# HS-IO_ESP32.net
KiCad netlist of a schematic drawn in Altium Designer
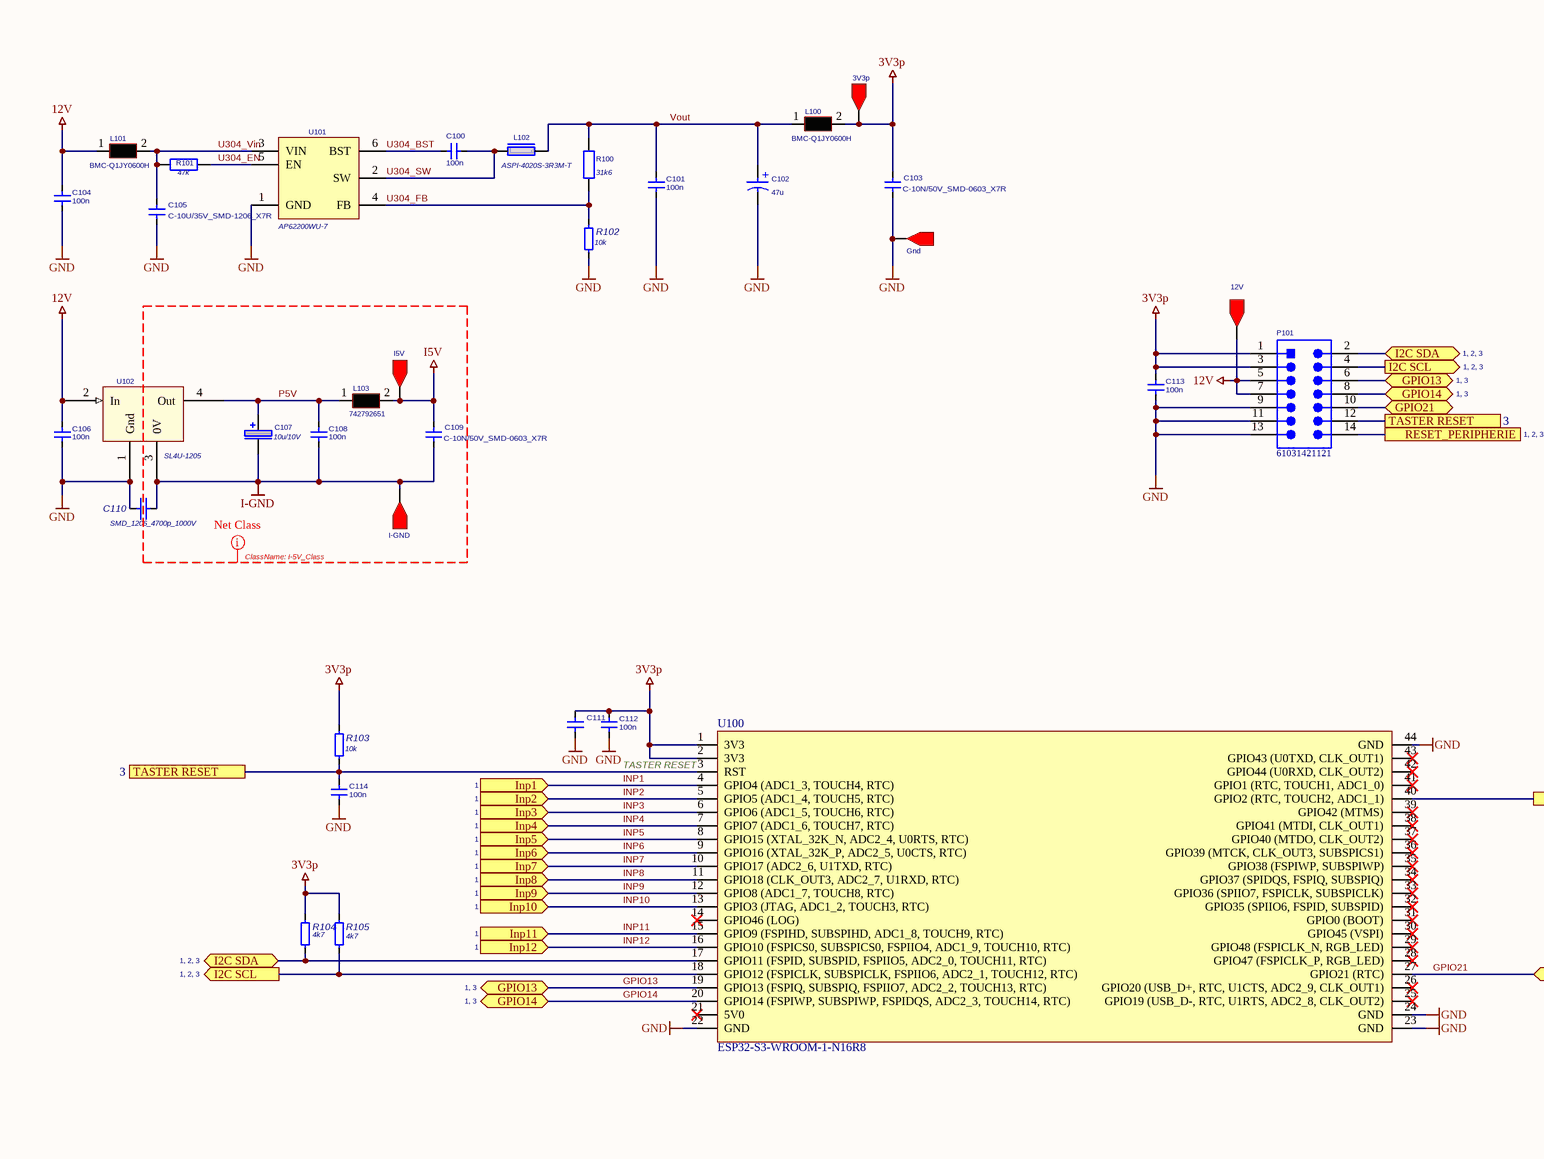
[diagram p0: HS-IO ESP32.SchDoc, left]
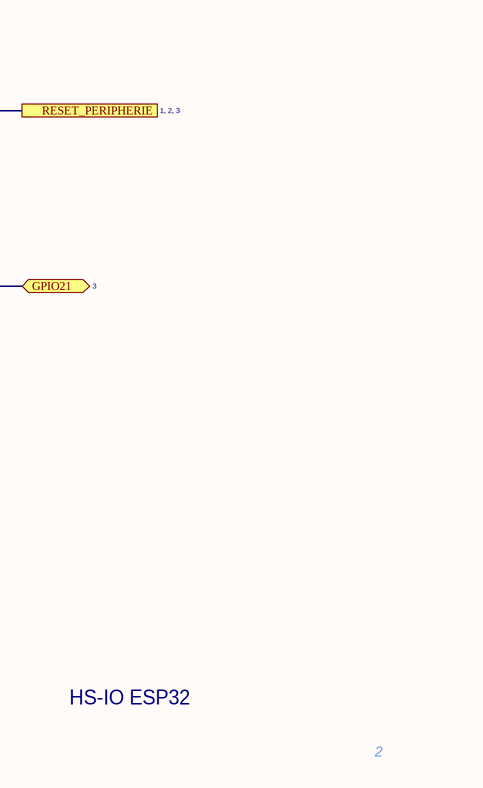
[diagram p1: HS-IO ESP32.SchDoc, right]

(export (version "E")
  (design (tool "Eeschema 10.0.6"))
  (components
    (comp (ref "3V3p")
      (value "(no part)")
      (footprint "TESTPOINT")
      (description "Test Point")
      (libsource (lib "FRAKO Kondensatoren- und Anlagenbau GmbH") (part "TESTPUNKT_1"))
    )
    (comp (ref "12V")
      (value "(no part)")
      (footprint "TESTPOINT")
      (description "Test Point")
      (libsource (lib "FRAKO Kondensatoren- und Anlagenbau GmbH") (part "TESTPUNKT_1"))
    )
    (comp (ref "C100")
      (value "100n")
      (footprint "CC1608-0603")
      (description "SMD0603, X7R, 15%, 50V, 100nF")
      (fields
        (field (name "MANUFACTURER") "KEMET")
        (field (name "MANUFACTURER PART NUMBER") "C0603C104K5RAC7867")
      )
      (libsource (lib "FRAKO Kondensatoren- und Anlagenbau GmbH") (part "C_SMD-0603"))
    )
    (comp (ref "C101")
      (value "100n")
      (footprint "CC1608-0603")
      (description "SMD0603, X7R, 15%, 50V, 100nF")
      (fields
        (field (name "MANUFACTURER") "KEMET")
        (field (name "MANUFACTURER PART NUMBER") "C0603C104K5RAC7867")
      )
      (libsource (lib "FRAKO Kondensatoren- und Anlagenbau GmbH") (part "C_SMD-0603"))
    )
    (comp (ref "C102")
      (value "47u")
      (footprint "WCAP-PSLP_D5H5.5")
      (description "WCAP-PSLP Aluminum Polymer Capacitor, V-Chip SMT, D5 x H5.5mm, 47µF, 6.3V")
      (fields
        (field (name "MANUFACTURER PART NUMBER") "875105142001")
        (field (name "MANUFACTURER") "Wurth Elektronik")
      )
      (libsource (lib "FRAKO Kondensatoren- und Anlagenbau GmbH") (part "875105945001"))
    )
    (comp (ref "C103")
      (value "C-10N/50V_SMD-0603_X7R")
      (footprint "0603_SMD_T")
      (description "C 10N/50V, SMD-0603, X7R")
      (fields
        (field (name "MANUFACTURER") "AVX GMBH")
        (field (name "MANUFACTURER PART NUMBER") "06035C103KAT2A")
      )
      (libsource (lib "FRAKO Kondensatoren- und Anlagenbau GmbH") (part "C_SMD-0603"))
    )
    (comp (ref "C104")
      (value "100n")
      (footprint "CC1608-0603")
      (description "SMD0603, X7R, 15%, 50V, 100nF")
      (fields
        (field (name "MANUFACTURER") "KEMET")
        (field (name "MANUFACTURER PART NUMBER") "C0603C104K5RAC7867")
      )
      (libsource (lib "FRAKO Kondensatoren- und Anlagenbau GmbH") (part "C_SMD-0603"))
    )
    (comp (ref "C105")
      (value "C-10U/35V_SMD-1206_X7R")
      (footprint "1206C_H0175_SMD_T")
      (description "Kondensator, MLCC, SMD 1206, 35V, 10uF, X7R,  10%")
      (fields
        (field (name "MANUFACTURER") "TAIYO YUDEN EUR")
        (field (name "MANUFACTURER PART NUMBER") "GMK316AB7106KL-TR")
      )
      (libsource (lib "FRAKO Kondensatoren- und Anlagenbau GmbH") (part "C_SMD-0603"))
    )
    (comp (ref "C106")
      (value "100n")
      (footprint "CC1608-0603")
      (description "SMD0603, X7R, 15%, 50V, 100nF")
      (fields
        (field (name "MANUFACTURER") "KEMET")
        (field (name "MANUFACTURER PART NUMBER") "C0603C104K5RAC7867")
      )
      (libsource (lib "FRAKO Kondensatoren- und Anlagenbau GmbH") (part "C_SMD-0603"))
    )
    (comp (ref "C107")
      (value "10u/10V")
      (footprint "TA-C")
      (description "Tantal Elko 10uF / 10V")
      (fields
        (field (name "MANUFACTURER") "KEMET")
        (field (name "MANUFACTURER PART NUMBER") "T491C106K010AT")
      )
      (libsource (lib "altium-import") (part "root_0_SMD_TAA_10u_1_"))
    )
    (comp (ref "C108")
      (value "100n")
      (footprint "CC1608-0603")
      (description "SMD0603, X7R, 15%, 50V, 100nF")
      (fields
        (field (name "MANUFACTURER") "KEMET")
        (field (name "MANUFACTURER PART NUMBER") "C0603C104K5RAC7867")
      )
      (libsource (lib "FRAKO Kondensatoren- und Anlagenbau GmbH") (part "C_SMD-0603"))
    )
    (comp (ref "C109")
      (value "C-10N/50V_SMD-0603_X7R")
      (footprint "0603_SMD_T")
      (description "C 10N/50V, SMD-0603, X7R")
      (fields
        (field (name "MANUFACTURER") "AVX GMBH")
        (field (name "MANUFACTURER PART NUMBER") "06035C103KAT2A")
      )
      (libsource (lib "FRAKO Kondensatoren- und Anlagenbau GmbH") (part "C_SMD-0603"))
    )
    (comp (ref "C110")
      (value "SMD_1206_4700p_1000V")
      (footprint "CR3216-1206")
      (description "Multilayer Ceramic Capacitors MLCC - SMD/SMT 1kV 4700pF X7R 1206 10%")
      (fields
        (field (name "MANUFACTURER") "YAGEO")
        (field (name "MANUFACTURER PART NUMBER") "CC1206KKX7RCBB472")
      )
      (libsource (lib "FRAKO Kondensatoren- und Anlagenbau GmbH") (part "Capacitor_SMD_1206"))
    )
    (comp (ref "C111")
      (value "C-10U/10V_SMD-0603_X5R")
      (footprint "CC1608-0603")
      (fields
        (field (name "MANUFACTURER") "TDK ELECTRONICS")
        (field (name "MANUFACTURER PART NUMBER") "C1608X5R1A106M080AC")
      )
      (libsource (lib "FRAKO Kondensatoren- und Anlagenbau GmbH") (part "C_SMD-0603"))
    )
    (comp (ref "C112")
      (value "100n")
      (footprint "CC1608-0603")
      (description "SMD0603, X7R, 15%, 50V, 100nF")
      (fields
        (field (name "MANUFACTURER") "KEMET")
        (field (name "MANUFACTURER PART NUMBER") "C0603C104K5RAC7867")
      )
      (libsource (lib "FRAKO Kondensatoren- und Anlagenbau GmbH") (part "C_SMD-0603"))
    )
    (comp (ref "C113")
      (value "100n")
      (footprint "CC1608-0603")
      (description "SMD0603, X7R, 15%, 50V, 100nF")
      (fields
        (field (name "MANUFACTURER") "KEMET")
        (field (name "MANUFACTURER PART NUMBER") "C0603C104K5RAC7867")
      )
      (libsource (lib "FRAKO Kondensatoren- und Anlagenbau GmbH") (part "C_SMD-0603"))
    )
    (comp (ref "C114")
      (value "100n")
      (footprint "CC1608-0603")
      (description "SMD0603, X7R, 15%, 50V, 100nF")
      (fields
        (field (name "MANUFACTURER") "KEMET")
        (field (name "MANUFACTURER PART NUMBER") "C0603C104K5RAC7867")
      )
      (libsource (lib "FRAKO Kondensatoren- und Anlagenbau GmbH") (part "C_SMD-0603"))
    )
    (comp (ref "Gnd")
      (value "(no part)")
      (footprint "TESTPOINT")
      (description "Test Point")
      (libsource (lib "FRAKO Kondensatoren- und Anlagenbau GmbH") (part "TESTPUNKT_1"))
    )
    (comp (ref "I-GND")
      (value "(no part)")
      (footprint "TESTPOINT")
      (description "Test Point")
      (libsource (lib "FRAKO Kondensatoren- und Anlagenbau GmbH") (part "TESTPUNKT_1"))
    )
    (comp (ref "I5V")
      (value "(no part)")
      (footprint "TESTPOINT")
      (description "Test Point")
      (libsource (lib "FRAKO Kondensatoren- und Anlagenbau GmbH") (part "TESTPUNKT_1"))
    )
    (comp (ref "L100")
      (value "BMC-Q1JY0600H")
      (footprint "0603-Ferrit")
      (description "Ferritperlen BMC-Q 0603 600R 25% Tol. High Current")
      (fields (field (name "MANUFACTURER") "TE Connectivity"))
      (libsource (lib "FRAKO Kondensatoren- und Anlagenbau GmbH") (part "Ferritperle"))
    )
    (comp (ref "L101")
      (value "BMC-Q1JY0600H")
      (footprint "0603-Ferrit")
      (description "Ferritperlen BMC-Q 0603 600R 25% Tol. High Current")
      (fields (field (name "MANUFACTURER") "TE Connectivity"))
      (libsource (lib "FRAKO Kondensatoren- und Anlagenbau GmbH") (part "Ferritperle"))
    )
    (comp (ref "L102")
      (value "ASPI-4020S-3R3M-T")
      (footprint "ASPI-4020S")
      (description "FIXED IND 3.3UH 1.34A 75MOHM SMD")
      (fields (field (name "MANUFACTURER") "ABRACON"))
      (libsource (lib "altium-import") (part "root_0_ASPI-4020S-3R3M-T_"))
    )
    (comp (ref "L103")
      (value "742792651")
      (footprint "0603-Ferrit")
      (description "Ferritperlen WE-CBF 0603 100MHz 600Ohm 1000mA AEC-Q200")
      (fields (field (name "MANUFACTURER") "Würth"))
      (libsource (lib "FRAKO Kondensatoren- und Anlagenbau GmbH") (part "Ferritperle"))
    )
    (comp (ref "P101")
      (value "61031421121")
      (footprint "61031421121")
      (description "WR-PHD Pin Header, SMT, pitch 2.54mm, Dual Row, Vertical, 14p")
      (fields (field (name "MANUFACTURER") "Wurth Elektronik"))
      (libsource (lib "FRAKO Kondensatoren- und Anlagenbau GmbH") (part "61031421121"))
    )
    (comp (ref "R100")
      (value "31k6")
      (footprint "CR1608-0603")
      (description "SMD0603, 0.1W, TK100, 1%, 31.6k")
      (fields
        (field (name "MANUFACTURER") "Vishay / Dale")
        (field (name "MANUFACTURER PART NUMBER") "CRCW060331K6FKEAC")
      )
      (libsource (lib "altium-import") (part "root_1_S0603_31k6_1_"))
    )
    (comp (ref "R101")
      (value "47k")
      (footprint "CR1608-0603")
      (description "RES 47K OHM 1% 1/10W 0603")
      (fields
        (field (name "MANUFACTURER") "Vishay / Dale")
        (field (name "MANUFACTURER PART NUMBER") "CRCW060347K0FKED")
      )
      (libsource (lib "altium-import") (part "root_2_S0603_47k_"))
    )
    (comp (ref "R102")
      (value "10k")
      (footprint "CR1608-0603")
      (description "SMD0603, 0.1W, TK100, 1%, 10k")
      (fields
        (field (name "MANUFACTURER") "Vishay / Dale")
        (field (name "MANUFACTURER PART NUMBER") "CRCW060310K0FKEAC")
      )
      (libsource (lib "FRAKO Kondensatoren- und Anlagenbau GmbH") (part "RES-EURO-S"))
    )
    (comp (ref "R103")
      (value "10k")
      (footprint "CR1608-0603")
      (description "SMD0603, 0.1W, TK100, 1%, 10k")
      (fields
        (field (name "MANUFACTURER") "Vishay / Dale")
        (field (name "MANUFACTURER PART NUMBER") "CRCW060310K0FKEAC")
      )
      (libsource (lib "FRAKO Kondensatoren- und Anlagenbau GmbH") (part "RES-EURO-S"))
    )
    (comp (ref "R104")
      (value "4k7")
      (footprint "CC1608-0603")
      (description "Dünnfilmwiderstände - SMD .1W 4.7Kohms 1% 0603 50ppm Auto")
      (fields
        (field (name "MANUFACTURER PART NUMBER") "MCT06030C4701FP500")
        (field (name "MANUFACTURER") "Vishay / Beyschlag")
      )
      (libsource (lib "FRAKO Kondensatoren- und Anlagenbau GmbH") (part "RES-EURO-S"))
    )
    (comp (ref "R105")
      (value "4k7")
      (footprint "CC1608-0603")
      (description "Dünnfilmwiderstände - SMD .1W 4.7Kohms 1% 0603 50ppm Auto")
      (fields
        (field (name "MANUFACTURER PART NUMBER") "MCT06030C4701FP500")
        (field (name "MANUFACTURER") "Vishay / Beyschlag")
      )
      (libsource (lib "FRAKO Kondensatoren- und Anlagenbau GmbH") (part "RES-EURO-S"))
    )
    (comp (ref "U100")
      (value "ESP32-S3-WROOM-1-N16R8")
      (footprint "DIL-44-ESP32")
      (description "SMD mod, ESP32-S3R8 with 3.3V, 8MB Octal PSRAM die insid, 6MBQuad SPI flash, pcb ant")
      (libsource (lib "FRAKO Kondensatoren- und Anlagenbau GmbH") (part "ESP32-S3-WROOM-1-MODUL"))
    )
    (comp (ref "U101")
      (value "AP62200WU-7")
      (footprint "SOT95P280X100-6N")
      (description "4.2V TO 18V INPUT, 2A LOW IQ SYNCHRONOUS BUCK CONVERTER")
      (fields (field (name "MANUFACTURER") "Diodes Incorporated"))
      (libsource (lib "altium-import") (part "root_0_AP62200WU-7_"))
    )
    (comp (ref "U102")
      (value "SL4U-1205")
      (footprint "SIP4_6mm")
      (description "DC/DC Wandler 1W 12V/5V Isolation 1000V")
      (fields (field (name "MANUFACTURER") "Floeth Electronic"))
      (libsource (lib "altium-import") (part "root_0_SL4U-1205_"))
    )
  )
  (nets
    (net (code "1") (name "/GPIO13") (class "Default")
      (node (ref "P101") (pin "6") (pinfunction "6_6") (pintype "passive"))
      (node (ref "U100") (pin "19") (pinfunction "GPIO13_(FSPIQ,_SUBSPIQ,_FSPIIO7,_ADC2_2,_TOUCH13,_RTC)_19") (pintype "passive"))
    )
    (net (code "2") (name "/GPIO14") (class "Default")
      (node (ref "P101") (pin "8") (pinfunction "8_8") (pintype "passive"))
      (node (ref "U100") (pin "20") (pinfunction "GPIO14_(FSPIWP,_SUBSPIWP,_FSPIDQS,_ADC2_3,_TOUCH14,_RTC)_20") (pintype "passive"))
    )
    (net (code "3") (name "/GPIO21") (class "Default")
      (node (ref "P101") (pin "10") (pinfunction "10_10") (pintype "passive"))
      (node (ref "U100") (pin "27") (pinfunction "GPIO21_(RTC)_27") (pintype "passive"))
    )
    (net (code "4") (name "/I2C SCL") (class "Default")
      (node (ref "P101") (pin "4") (pinfunction "4_4") (pintype "passive"))
      (node (ref "R105") (pin "1") (pinfunction "1_1") (pintype "passive"))
      (node (ref "U100") (pin "18") (pinfunction "GPIO12_(FSPICLK,_SUBSPICLK,_FSPIIO6,_ADC2_1,_TOUCH12,_RTC)_18") (pintype "passive"))
    )
    (net (code "5") (name "/I2C SDA") (class "Default")
      (node (ref "P101") (pin "2") (pinfunction "2_2") (pintype "passive"))
      (node (ref "R104") (pin "1") (pinfunction "1_1") (pintype "passive"))
      (node (ref "U100") (pin "17") (pinfunction "GPIO11_(FSPID,_SUBSPID,_FSPIIO5,_ADC2_0,_TOUCH11,_RTC)_17") (pintype "passive"))
    )
    (net (code "6") (name "/INP1") (class "Default")
      (node (ref "U100") (pin "4") (pinfunction "GPIO4_(ADC1_3,_TOUCH4,_RTC)_4") (pintype "passive"))
    )
    (net (code "7") (name "/INP2") (class "Default")
      (node (ref "U100") (pin "5") (pinfunction "GPIO5_(ADC1_4,_TOUCH5,_RTC)_5") (pintype "passive"))
    )
    (net (code "8") (name "/INP3") (class "Default")
      (node (ref "U100") (pin "6") (pinfunction "GPIO6_(ADC1_5,_TOUCH6,_RTC)_6") (pintype "passive"))
    )
    (net (code "9") (name "/INP4") (class "Default")
      (node (ref "U100") (pin "7") (pinfunction "GPIO7_(ADC1_6,_TOUCH7,_RTC)_7") (pintype "passive"))
    )
    (net (code "10") (name "/INP5") (class "Default")
      (node (ref "U100") (pin "8") (pinfunction "GPIO15_(XTAL_32K_N,_ADC2_4,_U0RTS,_RTC)_8") (pintype "passive"))
    )
    (net (code "11") (name "/INP6") (class "Default")
      (node (ref "U100") (pin "9") (pinfunction "GPIO16_(XTAL_32K_P,_ADC2_5,_U0CTS,_RTC)_9") (pintype "passive"))
    )
    (net (code "12") (name "/INP7") (class "Default")
      (node (ref "U100") (pin "10") (pinfunction "GPIO17_(ADC2_6,_U1TXD,_RTC)_10") (pintype "passive"))
    )
    (net (code "13") (name "/INP8") (class "Default")
      (node (ref "U100") (pin "11") (pinfunction "GPIO18_(CLK_OUT3,_ADC2_7,_U1RXD,_RTC)_11") (pintype "passive"))
    )
    (net (code "14") (name "/INP9") (class "Default")
      (node (ref "U100") (pin "12") (pinfunction "GPIO8_(ADC1_7,_TOUCH8,_RTC)_12") (pintype "passive"))
    )
    (net (code "15") (name "/INP10") (class "Default")
      (node (ref "U100") (pin "13") (pinfunction "GPIO3_(JTAG,_ADC1_2,_TOUCH3,_RTC)_13") (pintype "passive"))
    )
    (net (code "16") (name "/INP11") (class "Default")
      (node (ref "U100") (pin "15") (pinfunction "GPIO9_(FSPIHD,_SUBSPIHD,_ADC1_8,_TOUCH9,_RTC)_15") (pintype "passive"))
    )
    (net (code "17") (name "/INP12") (class "Default")
      (node (ref "U100") (pin "16") (pinfunction "GPIO10_(FSPICS0,_SUBSPICS0,_FSPIIO4,_ADC1_9,_TOUCH10,_RTC)_16") (pintype "passive"))
    )
    (net (code "18") (name "/P5V") (class "Default")
      (node (ref "C107") (pin "1") (pintype "passive"))
      (node (ref "C108") (pin "2") (pinfunction "2_2") (pintype "passive"))
      (node (ref "L103") (pin "1") (pinfunction "1_1") (pintype "passive"))
      (node (ref "U102") (pin "4") (pinfunction "Out_4") (pintype "power_in"))
    )
    (net (code "19") (name "/RESET_PERIPHERIE") (class "Default")
      (node (ref "P101") (pin "14") (pinfunction "14_14") (pintype "passive"))
      (node (ref "U100") (pin "40") (pinfunction "GPIO2_(RTC,_TOUCH2,_ADC1_1)_40") (pintype "passive"))
    )
    (net (code "20") (name "/TASTER RESET") (class "Default")
      (node (ref "C114") (pin "2") (pinfunction "2_2") (pintype "passive"))
      (node (ref "P101") (pin "12") (pinfunction "12_12") (pintype "passive"))
      (node (ref "R103") (pin "1") (pinfunction "1_1") (pintype "passive"))
      (node (ref "U100") (pin "3") (pinfunction "RST_3") (pintype "passive"))
    )
    (net (code "21") (name "/U304_BST") (class "Default")
      (node (ref "C100") (pin "1") (pinfunction "1_1") (pintype "passive"))
      (node (ref "U101") (pin "6") (pinfunction "BST_6") (pintype "passive"))
    )
    (net (code "22") (name "/U304_EN") (class "Default")
      (node (ref "R101") (pin "1") (pinfunction "1_1") (pintype "passive"))
      (node (ref "U101") (pin "5") (pinfunction "EN_5") (pintype "passive"))
    )
    (net (code "23") (name "/U304_FB") (class "Default")
      (node (ref "R100") (pin "1") (pinfunction "1_1") (pintype "passive"))
      (node (ref "R102") (pin "2") (pinfunction "2_2") (pintype "passive"))
      (node (ref "U101") (pin "4") (pinfunction "FB_4") (pintype "passive"))
    )
    (net (code "24") (name "/U304_SW") (class "Default")
      (node (ref "C100") (pin "2") (pinfunction "2_2") (pintype "passive"))
      (node (ref "L102") (pin "1") (pintype "passive"))
      (node (ref "U101") (pin "2") (pinfunction "SW_2") (pintype "passive"))
    )
    (net (code "25") (name "/U304_Vin") (class "Default")
      (node (ref "C105") (pin "1") (pinfunction "1_1") (pintype "passive"))
      (node (ref "L101") (pin "2") (pinfunction "2_2") (pintype "passive"))
      (node (ref "R101") (pin "2") (pinfunction "2_2") (pintype "passive"))
      (node (ref "U101") (pin "3") (pinfunction "VIN_3") (pintype "passive"))
    )
    (net (code "26") (name "/Vout") (class "Default")
      (node (ref "C101") (pin "2") (pinfunction "2_2") (pintype "passive"))
      (node (ref "C102") (pin "1") (pinfunction "P_1") (pintype "passive"))
      (node (ref "L100") (pin "1") (pinfunction "1_1") (pintype "passive"))
      (node (ref "L102") (pin "2") (pintype "passive"))
      (node (ref "R100") (pin "2") (pinfunction "2_2") (pintype "passive"))
    )
    (net (code "27") (name "3V3p") (class "Default")
      (node (ref "3V3p") (pin "1") (pintype "passive"))
      (node (ref "C103") (pin "1") (pinfunction "1_1") (pintype "passive"))
      (node (ref "C111") (pin "1") (pinfunction "1_1") (pintype "passive"))
      (node (ref "C112") (pin "2") (pinfunction "2_2") (pintype "passive"))
      (node (ref "C113") (pin "2") (pinfunction "2_2") (pintype "passive"))
      (node (ref "L100") (pin "2") (pinfunction "2_2") (pintype "passive"))
      (node (ref "P101") (pin "1") (pinfunction "1_1") (pintype "passive"))
      (node (ref "P101") (pin "3") (pinfunction "3_3") (pintype "passive"))
      (node (ref "R103") (pin "2") (pinfunction "2_2") (pintype "passive"))
      (node (ref "R104") (pin "2") (pinfunction "2_2") (pintype "passive"))
      (node (ref "R105") (pin "2") (pinfunction "2_2") (pintype "passive"))
      (node (ref "U100") (pin "1") (pinfunction "3V3_1") (pintype "passive"))
      (node (ref "U100") (pin "2") (pinfunction "3V3_2") (pintype "passive"))
    )
    (net (code "28") (name "12V") (class "Default")
      (node (ref "12V") (pin "1") (pintype "passive"))
      (node (ref "C104") (pin "1") (pinfunction "1_1") (pintype "passive"))
      (node (ref "C106") (pin "2") (pinfunction "2_2") (pintype "passive"))
      (node (ref "L101") (pin "1") (pinfunction "1_1") (pintype "passive"))
      (node (ref "P101") (pin "5") (pinfunction "5_5") (pintype "passive"))
      (node (ref "P101") (pin "7") (pinfunction "7_7") (pintype "passive"))
      (node (ref "U102") (pin "2") (pinfunction "In_2") (pintype "input"))
    )
    (net (code "29") (name "GND") (class "Default")
      (node (ref "C101") (pin "1") (pinfunction "1_1") (pintype "passive"))
      (node (ref "C102") (pin "2") (pinfunction "N_2") (pintype "passive"))
      (node (ref "C103") (pin "2") (pinfunction "2_2") (pintype "passive"))
      (node (ref "C104") (pin "2") (pinfunction "2_2") (pintype "passive"))
      (node (ref "C105") (pin "2") (pinfunction "2_2") (pintype "passive"))
      (node (ref "C106") (pin "1") (pinfunction "1_1") (pintype "passive"))
      (node (ref "C110") (pin "1") (pinfunction "1_1") (pintype "passive"))
      (node (ref "C111") (pin "2") (pinfunction "2_2") (pintype "passive"))
      (node (ref "C112") (pin "1") (pinfunction "1_1") (pintype "passive"))
      (node (ref "C113") (pin "1") (pinfunction "1_1") (pintype "passive"))
      (node (ref "C114") (pin "1") (pinfunction "1_1") (pintype "passive"))
      (node (ref "Gnd") (pin "1") (pintype "passive"))
      (node (ref "P101") (pin "11") (pinfunction "11_11") (pintype "passive"))
      (node (ref "P101") (pin "13") (pinfunction "13_13") (pintype "passive"))
      (node (ref "P101") (pin "9") (pinfunction "9_9") (pintype "passive"))
      (node (ref "R102") (pin "1") (pinfunction "1_1") (pintype "passive"))
      (node (ref "U100") (pin "22") (pinfunction "GND_22") (pintype "passive"))
      (node (ref "U100") (pin "23") (pinfunction "GND_23") (pintype "passive"))
      (node (ref "U100") (pin "24") (pinfunction "GND_24") (pintype "passive"))
      (node (ref "U100") (pin "44") (pinfunction "GND_44") (pintype "passive"))
      (node (ref "U101") (pin "1") (pinfunction "GND_1") (pintype "passive"))
      (node (ref "U102") (pin "1") (pinfunction "Gnd_1") (pintype "power_in"))
    )
    (net (code "30") (name "I-GND") (class "Default")
      (node (ref "C107") (pin "2") (pintype "passive"))
      (node (ref "C108") (pin "1") (pinfunction "1_1") (pintype "passive"))
      (node (ref "C109") (pin "2") (pinfunction "2_2") (pintype "passive"))
      (node (ref "C110") (pin "2") (pinfunction "2_2") (pintype "passive"))
      (node (ref "I-GND") (pin "1") (pintype "passive"))
      (node (ref "U102") (pin "3") (pinfunction "0V_3") (pintype "power_in"))
    )
    (net (code "31") (name "I5V") (class "Default")
      (node (ref "C109") (pin "1") (pinfunction "1_1") (pintype "passive"))
      (node (ref "I5V") (pin "1") (pintype "passive"))
      (node (ref "L103") (pin "2") (pinfunction "2_2") (pintype "passive"))
    )
    (net (code "32") (name "unconnected-(U100-5V0-Pad21)") (class "Default")
      (node (ref "U100") (pin "21") (pinfunction "5V0_21") (pintype "passive+no_connect"))
    )
    (net (code "33") (name "unconnected-(U100-GPIO0_(BOOT)-Pad31)") (class "Default")
      (node (ref "U100") (pin "31") (pinfunction "GPIO0_(BOOT)_31") (pintype "passive+no_connect"))
    )
    (net (code "34") (name "unconnected-(U100-GPIO1_(RTC,_TOUCH1,_ADC1_0)-Pad41)") (class "Default")
      (node (ref "U100") (pin "41") (pinfunction "GPIO1_(RTC,_TOUCH1,_ADC1_0)_41") (pintype "passive+no_connect"))
    )
    (net (code "35") (name "unconnected-(U100-GPIO19_(USB_D-,_RTC,_U1RTS,_ADC2_8,_CLK_OUT2)-Pad25)") (class "Default")
      (node (ref "U100") (pin "25") (pinfunction "GPIO19_(USB_D-,_RTC,_U1RTS,_ADC2_8,_CLK_OUT2)_25") (pintype "passive+no_connect"))
    )
    (net (code "36") (name "unconnected-(U100-GPIO20_(USB_D+,_RTC,_U1CTS,_ADC2_9,_CLK_OUT1)-Pad26)") (class "Default")
      (node (ref "U100") (pin "26") (pinfunction "GPIO20_(USB_D+,_RTC,_U1CTS,_ADC2_9,_CLK_OUT1)_26") (pintype "passive+no_connect"))
    )
    (net (code "37") (name "unconnected-(U100-GPIO35_(SPIIO6,_FSPID,_SUBSPID)-Pad32)") (class "Default")
      (node (ref "U100") (pin "32") (pinfunction "GPIO35_(SPIIO6,_FSPID,_SUBSPID)_32") (pintype "passive+no_connect"))
    )
    (net (code "38") (name "unconnected-(U100-GPIO36_(SPIIO7,_FSPICLK,_SUBSPICLK)-Pad33)") (class "Default")
      (node (ref "U100") (pin "33") (pinfunction "GPIO36_(SPIIO7,_FSPICLK,_SUBSPICLK)_33") (pintype "passive+no_connect"))
    )
    (net (code "39") (name "unconnected-(U100-GPIO37_(SPIDQS,_FSPIQ,_SUBSPIQ)-Pad34)") (class "Default")
      (node (ref "U100") (pin "34") (pinfunction "GPIO37_(SPIDQS,_FSPIQ,_SUBSPIQ)_34") (pintype "passive+no_connect"))
    )
    (net (code "40") (name "unconnected-(U100-GPIO38_(FSPIWP,_SUBSPIWP)-Pad35)") (class "Default")
      (node (ref "U100") (pin "35") (pinfunction "GPIO38_(FSPIWP,_SUBSPIWP)_35") (pintype "passive+no_connect"))
    )
    (net (code "41") (name "unconnected-(U100-GPIO39_(MTCK,_CLK_OUT3,_SUBSPICS1)-Pad36)") (class "Default")
      (node (ref "U100") (pin "36") (pinfunction "GPIO39_(MTCK,_CLK_OUT3,_SUBSPICS1)_36") (pintype "passive+no_connect"))
    )
    (net (code "42") (name "unconnected-(U100-GPIO40_(MTDO,_CLK_OUT2)-Pad37)") (class "Default")
      (node (ref "U100") (pin "37") (pinfunction "GPIO40_(MTDO,_CLK_OUT2)_37") (pintype "passive+no_connect"))
    )
    (net (code "43") (name "unconnected-(U100-GPIO41_(MTDI,_CLK_OUT1)-Pad38)") (class "Default")
      (node (ref "U100") (pin "38") (pinfunction "GPIO41_(MTDI,_CLK_OUT1)_38") (pintype "passive+no_connect"))
    )
    (net (code "44") (name "unconnected-(U100-GPIO42_(MTMS)-Pad39)") (class "Default")
      (node (ref "U100") (pin "39") (pinfunction "GPIO42_(MTMS)_39") (pintype "passive+no_connect"))
    )
    (net (code "45") (name "unconnected-(U100-GPIO43_(U0TXD,_CLK_OUT1)-Pad43)") (class "Default")
      (node (ref "U100") (pin "43") (pinfunction "GPIO43_(U0TXD,_CLK_OUT1)_43") (pintype "passive+no_connect"))
    )
    (net (code "46") (name "unconnected-(U100-GPIO44_(U0RXD,_CLK_OUT2)-Pad42)") (class "Default")
      (node (ref "U100") (pin "42") (pinfunction "GPIO44_(U0RXD,_CLK_OUT2)_42") (pintype "passive+no_connect"))
    )
    (net (code "47") (name "unconnected-(U100-GPIO45_(VSPI)-Pad30)") (class "Default")
      (node (ref "U100") (pin "30") (pinfunction "GPIO45_(VSPI)_30") (pintype "passive+no_connect"))
    )
    (net (code "48") (name "unconnected-(U100-GPIO46_(LOG)-Pad14)") (class "Default")
      (node (ref "U100") (pin "14") (pinfunction "GPIO46_(LOG)_14") (pintype "passive+no_connect"))
    )
    (net (code "49") (name "unconnected-(U100-GPIO47_(FSPICLK_P,_RGB_LED)-Pad28)") (class "Default")
      (node (ref "U100") (pin "28") (pinfunction "GPIO47_(FSPICLK_P,_RGB_LED)_28") (pintype "passive+no_connect"))
    )
    (net (code "50") (name "unconnected-(U100-GPIO48_(FSPICLK_N,_RGB_LED)-Pad29)") (class "Default")
      (node (ref "U100") (pin "29") (pinfunction "GPIO48_(FSPICLK_N,_RGB_LED)_29") (pintype "passive+no_connect"))
    )
  )
)
